# DC_Control.net
KiCad netlist of a schematic drawn in Altium Designer
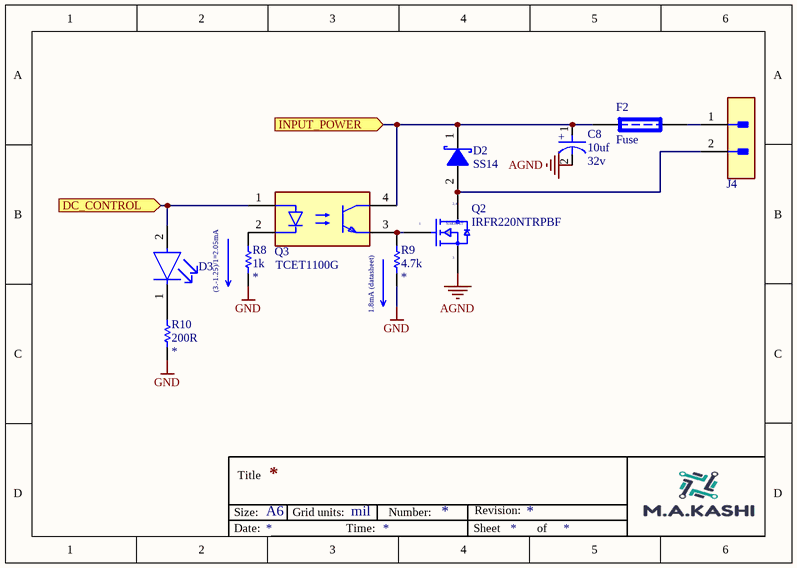
[diagram p0: DC_Control.SchDoc]

(export (version "E")
  (design (tool "Eeschema 10.0.6"))
  (components
    (comp (ref "C8")
      (value "Capacitor Electrolytic")
      (footprint "CAP_electrolitic_5x5.4_Panasonic")
      (fields (field (name "CAPACITANCE") "10uf") (field (name "VOLTAGE") "32v"))
      (libsource (lib "E-component") (part "Capacitor Electrolytic"))
    )
    (comp (ref "D2")
      (value "SS14")
      (footprint "SS26FL_SS24FL_ONSemi_A")
      (libsource (lib "E-component") (part "Schottky Diode"))
    )
    (comp (ref "D3")
      (value "LED")
      (footprint "LED_0805_green_Dialight")
      (fields (field (name "PART NUMBER") "Add part number!"))
      (libsource (lib "E-component") (part "LED"))
    )
    (comp (ref "F2")
      (value "Fuse")
      (footprint "FUSE")
      (fields (field (name "PUBLISHER") "Altium Limited"))
      (libsource (lib "E-component") (part "Fuse"))
    )
    (comp (ref "J4")
      (value "Connector")
      (footprint "Phoenix 2 0D")
      (fields (field (name "MANUFACTURER") "JST") (field (name "DIGIKEY PART NUMBER") "455-2247-ND"))
      (libsource (lib "E-component") (part "Connector 2 pin"))
    )
    (comp (ref "Q2")
      (value "IRFR220NTRPBF")
      (footprint "Infineon_PG-TO252-3_MFG")
      (fields (field (name "PART NUMBER") "DMP3099L-13"))
      (libsource (lib "E-component") (part "IRFR220NTRPBF"))
    )
    (comp (ref "Q3")
      (value "TCET1100G")
      (footprint "DIP-4")
      (libsource (lib "E-component") (part "Optocoupler-1ch"))
    )
    (comp (ref "R8")
      (value "1k")
      (footprint "RES_0805_A")
      (description "octopart or digikey description!")
      (fields (field (name "TOLERANCE") "*"))
      (libsource (lib "E-component") (part "Resistor"))
    )
    (comp (ref "R9")
      (value "4.7k")
      (footprint "RES_0805_A")
      (description "octopart or digikey description!")
      (fields (field (name "TOLERANCE") "*"))
      (libsource (lib "E-component") (part "Resistor"))
    )
    (comp (ref "R10")
      (value "200R")
      (footprint "RES_0805_A")
      (description "octopart or digikey description!")
      (fields (field (name "TOLERANCE") "*"))
      (libsource (lib "E-component") (part "Resistor"))
    )
  )
  (nets
    (net (code "1") (name "/DC_CONTROL") (class "Default")
      (node (ref "D3") (pin "2") (pinfunction "A_2") (pintype "passive"))
      (node (ref "Q3") (pin "1") (pinfunction "A_1") (pintype "passive"))
    )
    (net (code "2") (name "/INPUT_POWER") (class "Default")
      (node (ref "C8") (pin "1") (pinfunction "C_1") (pintype "passive"))
      (node (ref "D2") (pin "1") (pinfunction "Cathode_1") (pintype "passive"))
      (node (ref "F2") (pin "1") (pinfunction "1_1") (pintype "passive"))
      (node (ref "Q3") (pin "4") (pinfunction "C_4") (pintype "passive"))
    )
    (net (code "3") (name "AGND") (class "Default")
      (node (ref "C8") (pin "2") (pinfunction "A_2") (pintype "passive"))
      (node (ref "Q2") (pin "3") (pinfunction "S_3") (pintype "passive"))
    )
    (net (code "4") (name "GND") (class "Default")
      (node (ref "R10") (pin "2") (pinfunction "2_2") (pintype "passive"))
      (node (ref "R8") (pin "2") (pinfunction "2_2") (pintype "passive"))
      (node (ref "R9") (pin "2") (pinfunction "2_2") (pintype "passive"))
    )
    (net (code "5") (name "Net-(D2-Anode)") (class "Default")
      (node (ref "D2") (pin "2") (pinfunction "Anode_2") (pintype "passive"))
      (node (ref "J4") (pin "2") (pinfunction "2_2") (pintype "passive"))
      (node (ref "Q2") (pin "4") (pinfunction "D_4") (pintype "passive"))
    )
    (net (code "6") (name "Net-(D3-C)") (class "Default")
      (node (ref "D3") (pin "1") (pinfunction "C_1") (pintype "passive"))
      (node (ref "R10") (pin "1") (pinfunction "1_1") (pintype "passive"))
    )
    (net (code "7") (name "Net-(F2-Pad2)") (class "Default")
      (node (ref "F2") (pin "2") (pinfunction "2_2") (pintype "passive"))
      (node (ref "J4") (pin "1") (pinfunction "1_1") (pintype "passive"))
    )
    (net (code "8") (name "Net-(Q2-G)") (class "Default")
      (node (ref "Q2") (pin "1") (pinfunction "G_1") (pintype "passive"))
      (node (ref "Q3") (pin "3") (pinfunction "E_3") (pintype "passive"))
      (node (ref "R9") (pin "1") (pinfunction "1_1") (pintype "passive"))
    )
    (net (code "9") (name "Net-(Q3-C-Pad2)") (class "Default")
      (node (ref "Q3") (pin "2") (pinfunction "C_2") (pintype "passive"))
      (node (ref "R8") (pin "1") (pinfunction "1_1") (pintype "passive"))
    )
  )
)
